# HyperRAM.net
KiCad netlist of a schematic drawn in Altium Designer
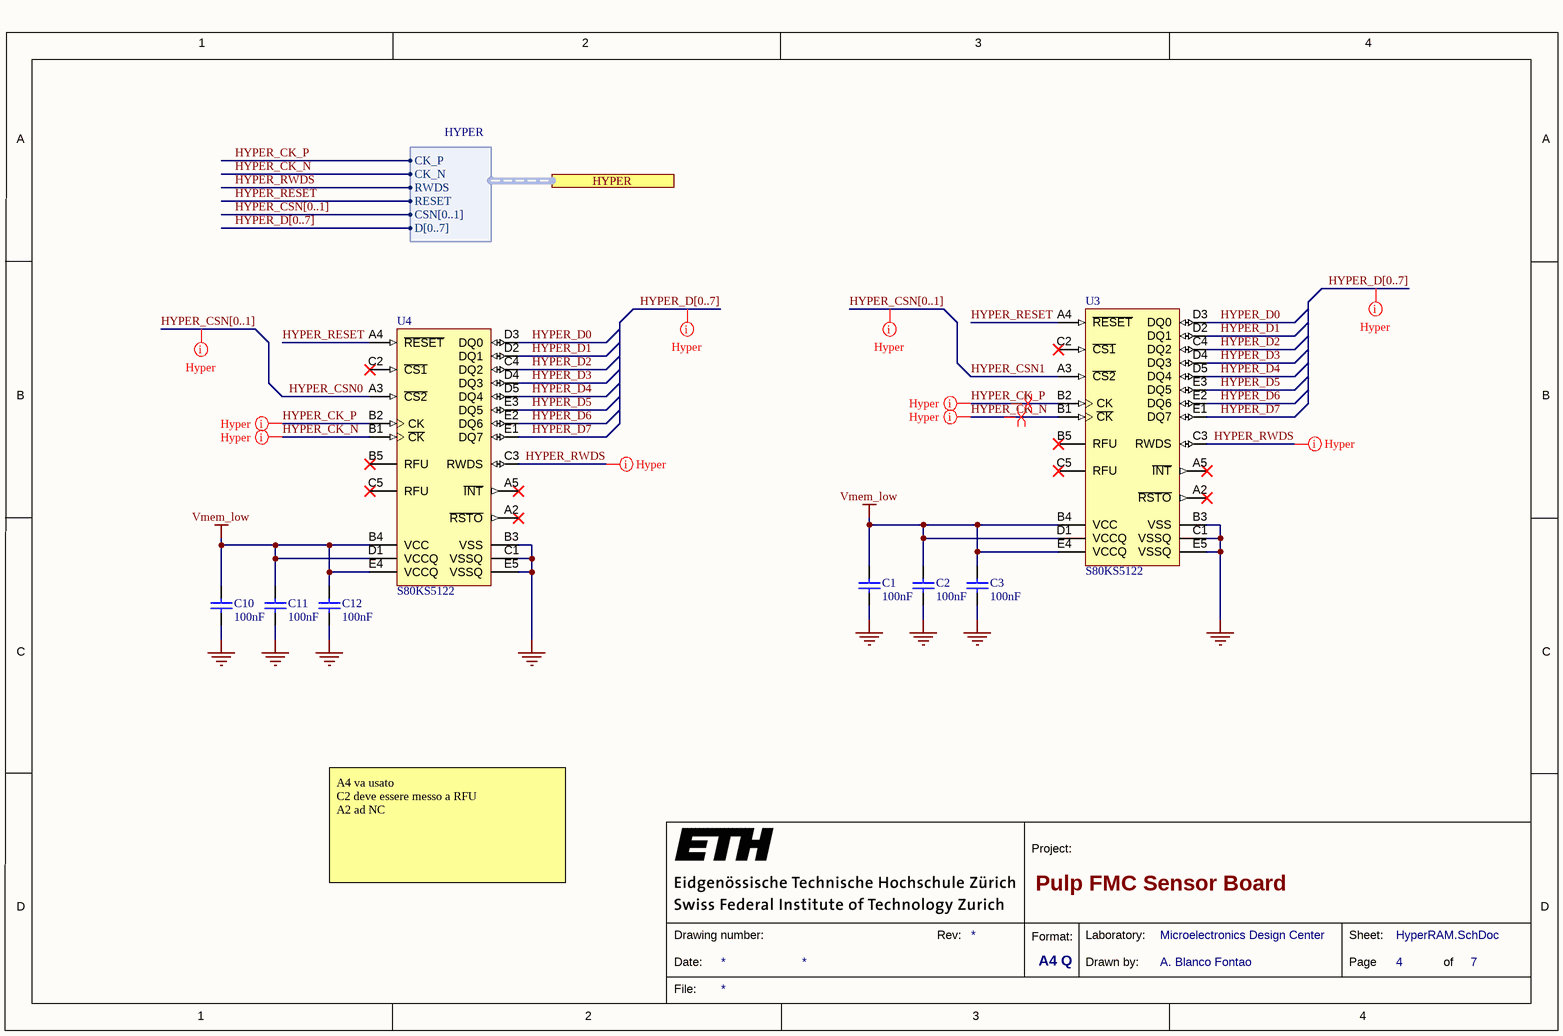
[diagram p0: HyperRAM.SchDoc]

(export (version "E")
  (design (tool "Eeschema 10.0.6"))
  (components
    (comp (ref "C1")
      (value "100nF")
      (footprint "CAPC0603(1608)100_N")
      (description "CAP 100nF 25V ±10% 0603 (1608 Metric) Thickness 1mm SMD")
      (fields (field (name "TOLERANCE") "Â±10%") (field (name "Comment") "CAP 100nF 25V 0603(1608)"))
      (libsource (lib "Altium Content Vault") (part "CMP-1035-02588-1"))
    )
    (comp (ref "C2")
      (value "100nF")
      (footprint "CAPC0603(1608)100_N")
      (description "CAP 100nF 25V ±10% 0603 (1608 Metric) Thickness 1mm SMD")
      (fields (field (name "TOLERANCE") "Â±10%") (field (name "Comment") "CAP 100nF 25V 0603(1608)"))
      (libsource (lib "Altium Content Vault") (part "CMP-1035-02588-1"))
    )
    (comp (ref "C3")
      (value "100nF")
      (footprint "CAPC0603(1608)100_N")
      (description "CAP 100nF 25V ±10% 0603 (1608 Metric) Thickness 1mm SMD")
      (fields (field (name "TOLERANCE") "Â±10%") (field (name "Comment") "CAP 100nF 25V 0603(1608)"))
      (libsource (lib "Altium Content Vault") (part "CMP-1035-02588-1"))
    )
    (comp (ref "C10")
      (value "100nF")
      (footprint "CAPC0603(1608)100_N")
      (description "CAP 100nF 25V ±10% 0603 (1608 Metric) Thickness 1mm SMD")
      (fields (field (name "TOLERANCE") "Â±10%") (field (name "Comment") "CAP 100nF 25V 0603(1608)"))
      (libsource (lib "Altium Content Vault") (part "CMP-1035-02588-1"))
    )
    (comp (ref "C11")
      (value "100nF")
      (footprint "CAPC0603(1608)100_N")
      (description "CAP 100nF 25V ±10% 0603 (1608 Metric) Thickness 1mm SMD")
      (fields (field (name "TOLERANCE") "Â±10%") (field (name "Comment") "CAP 100nF 25V 0603(1608)"))
      (libsource (lib "Altium Content Vault") (part "CMP-1035-02588-1"))
    )
    (comp (ref "C12")
      (value "100nF")
      (footprint "CAPC0603(1608)100_N")
      (description "CAP 100nF 25V ±10% 0603 (1608 Metric) Thickness 1mm SMD")
      (fields (field (name "TOLERANCE") "Â±10%") (field (name "Comment") "CAP 100nF 25V 0603(1608)"))
      (libsource (lib "Altium Content Vault") (part "CMP-1035-02588-1"))
    )
    (comp (ref "U3")
      (value "S80KS5122")
      (footprint "FBGA24_A-130")
      (description "512 Mb: HYPERRAM™ self-refresh dynamic\r\n RAM (DRAM) with HYPERBUS™ interface\r\n 1.8 V")
      (fields (field (name "MANUFACTURER") "Cypress Semiconductor Corp"))
      (libsource (lib "Pulp FMC Sensor Board") (part "CMP-00514-1"))
    )
    (comp (ref "U4")
      (value "S80KS5122")
      (footprint "FBGA24_A-130")
      (description "512 Mb: HYPERRAM™ self-refresh dynamic\r\n RAM (DRAM) with HYPERBUS™ interface\r\n 1.8 V")
      (fields (field (name "MANUFACTURER") "Cypress Semiconductor Corp"))
      (libsource (lib "Pulp FMC Sensor Board") (part "CMP-00514-1"))
    )
  )
  (nets
    (net (code "2") (name "/HYPER_CK_N") (class "Default")
      (node (ref "U3") (pin "B1") (pinfunction "~{CK}_B1") (pintype "input"))
      (node (ref "U4") (pin "B1") (pinfunction "~{CK}_B1") (pintype "input"))
    )
    (net (code "3") (name "/HYPER_CK_P") (class "Default")
      (node (ref "U3") (pin "B2") (pinfunction "CK_B2") (pintype "input"))
      (node (ref "U4") (pin "B2") (pinfunction "CK_B2") (pintype "input"))
    )
    (net (code "4") (name "/HYPER_CSN0") (class "Default")
      (node (ref "U4") (pin "A3") (pinfunction "~{CS2}_A3") (pintype "input"))
    )
    (net (code "5") (name "/HYPER_CSN1") (class "Default")
      (node (ref "U3") (pin "A3") (pinfunction "~{CS2}_A3") (pintype "input"))
    )
    (net (code "7") (name "/HYPER_D0") (class "Default")
      (node (ref "U3") (pin "D3") (pinfunction "DQ0_D3") (pintype "bidirectional"))
      (node (ref "U4") (pin "D3") (pinfunction "DQ0_D3") (pintype "bidirectional"))
    )
    (net (code "8") (name "/HYPER_D1") (class "Default")
      (node (ref "U3") (pin "D2") (pinfunction "DQ1_D2") (pintype "bidirectional"))
      (node (ref "U4") (pin "D2") (pinfunction "DQ1_D2") (pintype "bidirectional"))
    )
    (net (code "9") (name "/HYPER_D2") (class "Default")
      (node (ref "U3") (pin "C4") (pinfunction "DQ2_C4") (pintype "bidirectional"))
      (node (ref "U4") (pin "C4") (pinfunction "DQ2_C4") (pintype "bidirectional"))
    )
    (net (code "10") (name "/HYPER_D3") (class "Default")
      (node (ref "U3") (pin "D4") (pinfunction "DQ3_D4") (pintype "bidirectional"))
      (node (ref "U4") (pin "D4") (pinfunction "DQ3_D4") (pintype "bidirectional"))
    )
    (net (code "11") (name "/HYPER_D4") (class "Default")
      (node (ref "U3") (pin "D5") (pinfunction "DQ4_D5") (pintype "bidirectional"))
      (node (ref "U4") (pin "D5") (pinfunction "DQ4_D5") (pintype "bidirectional"))
    )
    (net (code "12") (name "/HYPER_D5") (class "Default")
      (node (ref "U3") (pin "E3") (pinfunction "DQ5_E3") (pintype "bidirectional"))
      (node (ref "U4") (pin "E3") (pinfunction "DQ5_E3") (pintype "bidirectional"))
    )
    (net (code "13") (name "/HYPER_D6") (class "Default")
      (node (ref "U3") (pin "E2") (pinfunction "DQ6_E2") (pintype "bidirectional"))
      (node (ref "U4") (pin "E2") (pinfunction "DQ6_E2") (pintype "bidirectional"))
    )
    (net (code "14") (name "/HYPER_D7") (class "Default")
      (node (ref "U3") (pin "E1") (pinfunction "DQ7_E1") (pintype "bidirectional"))
      (node (ref "U4") (pin "E1") (pinfunction "DQ7_E1") (pintype "bidirectional"))
    )
    (net (code "16") (name "/HYPER_RESET") (class "Default")
      (node (ref "U3") (pin "A4") (pinfunction "~{RESET}_A4") (pintype "input"))
      (node (ref "U4") (pin "A4") (pinfunction "~{RESET}_A4") (pintype "input"))
    )
    (net (code "17") (name "/HYPER_RWDS") (class "Default")
      (node (ref "U3") (pin "C3") (pinfunction "RWDS_C3") (pintype "bidirectional"))
      (node (ref "U4") (pin "C3") (pinfunction "RWDS_C3") (pintype "bidirectional"))
    )
    (net (code "19") (name "GND") (class "Default")
      (node (ref "C1") (pin "1") (pinfunction "1_1") (pintype "passive"))
      (node (ref "C10") (pin "1") (pinfunction "1_1") (pintype "passive"))
      (node (ref "C11") (pin "1") (pinfunction "1_1") (pintype "passive"))
      (node (ref "C12") (pin "1") (pinfunction "1_1") (pintype "passive"))
      (node (ref "C2") (pin "1") (pinfunction "1_1") (pintype "passive"))
      (node (ref "C3") (pin "1") (pinfunction "1_1") (pintype "passive"))
      (node (ref "U3") (pin "B3") (pinfunction "VSS_B3") (pintype "power_in"))
      (node (ref "U3") (pin "C1") (pinfunction "VSSQ_C1") (pintype "power_in"))
      (node (ref "U3") (pin "E5") (pinfunction "VSSQ_E5") (pintype "power_in"))
      (node (ref "U4") (pin "B3") (pinfunction "VSS_B3") (pintype "power_in"))
      (node (ref "U4") (pin "C1") (pinfunction "VSSQ_C1") (pintype "power_in"))
      (node (ref "U4") (pin "E5") (pinfunction "VSSQ_E5") (pintype "power_in"))
    )
    (net (code "20") (name "Vmem_low") (class "Default")
      (node (ref "C1") (pin "2") (pinfunction "2_2") (pintype "passive"))
      (node (ref "C10") (pin "2") (pinfunction "2_2") (pintype "passive"))
      (node (ref "C11") (pin "2") (pinfunction "2_2") (pintype "passive"))
      (node (ref "C12") (pin "2") (pinfunction "2_2") (pintype "passive"))
      (node (ref "C2") (pin "2") (pinfunction "2_2") (pintype "passive"))
      (node (ref "C3") (pin "2") (pinfunction "2_2") (pintype "passive"))
      (node (ref "U3") (pin "B4") (pinfunction "VCC_B4") (pintype "power_in"))
      (node (ref "U3") (pin "D1") (pinfunction "VCCQ_D1") (pintype "power_in"))
      (node (ref "U3") (pin "E4") (pinfunction "VCCQ_E4") (pintype "power_in"))
      (node (ref "U4") (pin "B4") (pinfunction "VCC_B4") (pintype "power_in"))
      (node (ref "U4") (pin "D1") (pinfunction "VCCQ_D1") (pintype "power_in"))
      (node (ref "U4") (pin "E4") (pinfunction "VCCQ_E4") (pintype "power_in"))
    )
    (net (code "21") (name "unconnected-(U3-RFU-PadB5)") (class "Default")
      (node (ref "U3") (pin "B5") (pinfunction "RFU_B5") (pintype "passive+no_connect"))
    )
    (net (code "22") (name "unconnected-(U3-RFU-PadC5)") (class "Default")
      (node (ref "U3") (pin "C5") (pinfunction "RFU_C5") (pintype "passive+no_connect"))
    )
    (net (code "23") (name "unconnected-(U3-~{CS1}-PadC2)") (class "Default")
      (node (ref "U3") (pin "C2") (pinfunction "~{CS1}_C2") (pintype "input+no_connect"))
    )
    (net (code "24") (name "unconnected-(U3-~{INT}-PadA5)") (class "Default")
      (node (ref "U3") (pin "A5") (pinfunction "~{INT}_A5") (pintype "output+no_connect"))
    )
    (net (code "25") (name "unconnected-(U3-~{RSTO}-PadA2)") (class "Default")
      (node (ref "U3") (pin "A2") (pinfunction "~{RSTO}_A2") (pintype "output+no_connect"))
    )
    (net (code "26") (name "unconnected-(U4-RFU-PadB5)") (class "Default")
      (node (ref "U4") (pin "B5") (pinfunction "RFU_B5") (pintype "passive+no_connect"))
    )
    (net (code "27") (name "unconnected-(U4-RFU-PadC5)") (class "Default")
      (node (ref "U4") (pin "C5") (pinfunction "RFU_C5") (pintype "passive+no_connect"))
    )
    (net (code "28") (name "unconnected-(U4-~{CS1}-PadC2)") (class "Default")
      (node (ref "U4") (pin "C2") (pinfunction "~{CS1}_C2") (pintype "input+no_connect"))
    )
    (net (code "29") (name "unconnected-(U4-~{INT}-PadA5)") (class "Default")
      (node (ref "U4") (pin "A5") (pinfunction "~{INT}_A5") (pintype "output+no_connect"))
    )
    (net (code "30") (name "unconnected-(U4-~{RSTO}-PadA2)") (class "Default")
      (node (ref "U4") (pin "A2") (pinfunction "~{RSTO}_A2") (pintype "output+no_connect"))
    )
  )
)
